# nano_hold_1_2.net
KiCad netlist of a schematic drawn in EAGLE
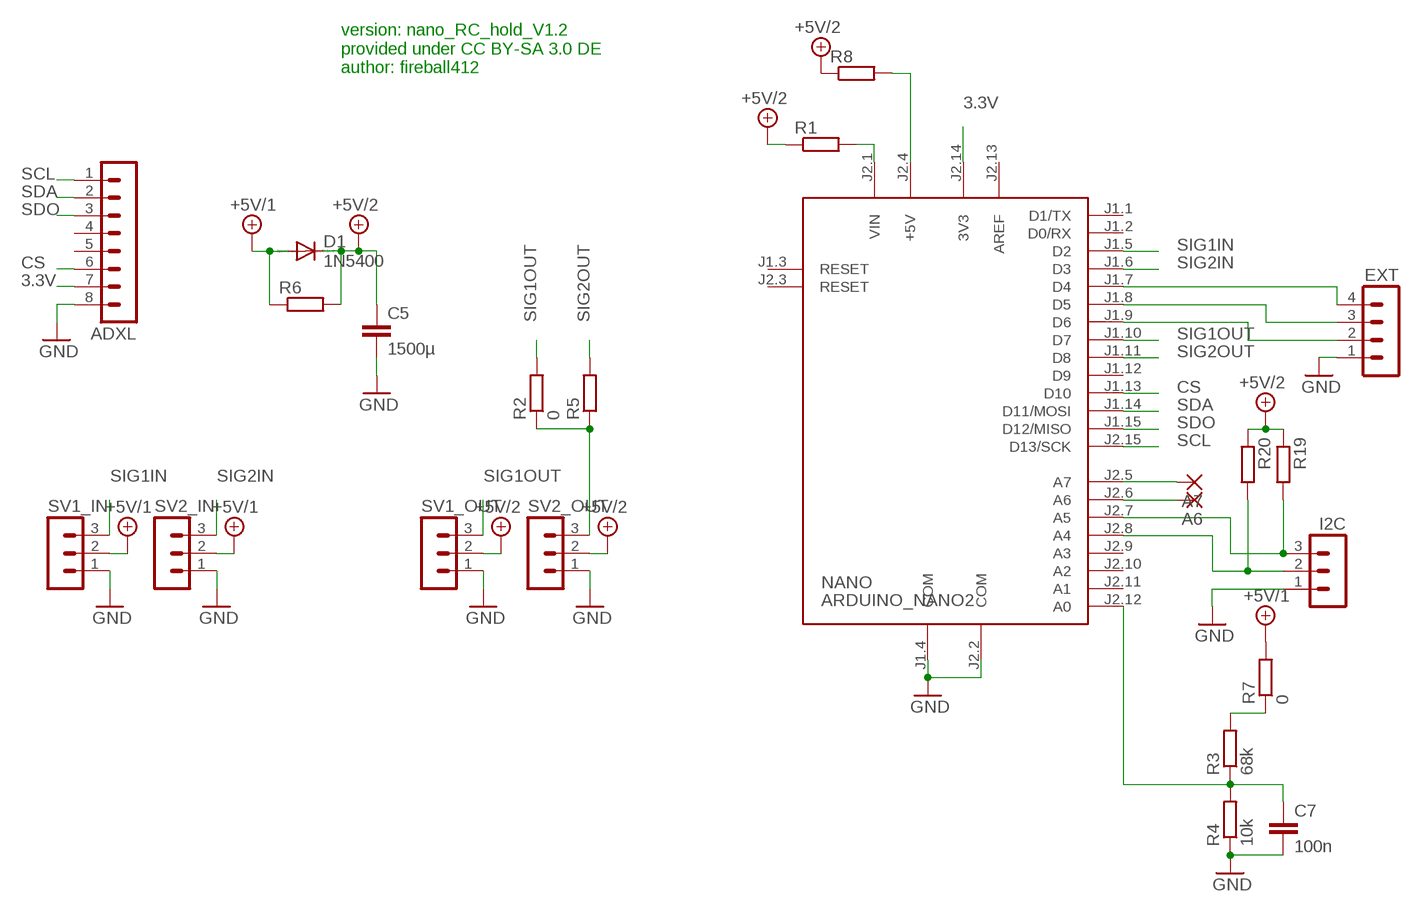
[diagram p0: schematic, sheet 1]

(export (version "E")
  (design (tool "Eeschema 10.0.6"))
  (components
    (comp (ref "A6")
      (value "WIREPAD2,15/1,0")
      (footprint "eagle-import:2,15_1,0")
      (libsource (lib "eagle-import") (part "WIREPAD2,15/1,0"))
    )
    (comp (ref "A7")
      (value "WIREPAD2,15/1,0")
      (footprint "eagle-import:2,15_1,0")
      (libsource (lib "eagle-import") (part "WIREPAD2,15/1,0"))
    )
    (comp (ref "ADXL")
      (value "MA08-1")
      (footprint "eagle-import:MA08-1")
      (libsource (lib "eagle-import") (part "MA08-1"))
    )
    (comp (ref "C5")
      (value "1500µ")
      (footprint "eagle-import:C050H075X075")
      (libsource (lib "eagle-import") (part "C-EU050H075X075"))
    )
    (comp (ref "C7")
      (value "100n")
      (footprint "eagle-import:C0805")
      (libsource (lib "eagle-import") (part "C-EUC0805"))
    )
    (comp (ref "D1")
      (value "1N5400")
      (footprint "eagle-import:DO201-15")
      (libsource (lib "eagle-import") (part "1N5400"))
    )
    (comp (ref "EXT")
      (value "MA04-1")
      (footprint "eagle-import:MA04-1")
      (libsource (lib "eagle-import") (part "MA04-1"))
    )
    (comp (ref "I2C")
      (value "MA03-1")
      (footprint "eagle-import:MA03-1")
      (libsource (lib "eagle-import") (part "MA03-1"))
    )
    (comp (ref "NANO")
      (value "ARDUINO_NANO2")
      (footprint "eagle-import:ARDUINO_NANO2")
      (libsource (lib "eagle-import") (part "ARDUINO_NANO2"))
    )
    (comp (ref "R1")
      (value "R-EU_R0805")
      (footprint "eagle-import:R0805")
      (libsource (lib "eagle-import") (part "R-EU_R0805"))
    )
    (comp (ref "R2")
      (value "0")
      (footprint "eagle-import:R0805")
      (libsource (lib "eagle-import") (part "R-EU_R0805"))
    )
    (comp (ref "R3")
      (value "68k")
      (footprint "eagle-import:R0805")
      (libsource (lib "eagle-import") (part "R-EU_R0805"))
    )
    (comp (ref "R4")
      (value "10k")
      (footprint "eagle-import:R0805")
      (libsource (lib "eagle-import") (part "R-EU_R0805"))
    )
    (comp (ref "R5")
      (value "R-EU_R0805")
      (footprint "eagle-import:R0805")
      (libsource (lib "eagle-import") (part "R-EU_R0805"))
    )
    (comp (ref "R6")
      (value "R-EU_R0805")
      (footprint "eagle-import:R0805")
      (libsource (lib "eagle-import") (part "R-EU_R0805"))
    )
    (comp (ref "R7")
      (value "0")
      (footprint "eagle-import:R0805")
      (libsource (lib "eagle-import") (part "R-EU_R0805"))
    )
    (comp (ref "R8")
      (value "R-EU_R0805")
      (footprint "eagle-import:R0805")
      (libsource (lib "eagle-import") (part "R-EU_R0805"))
    )
    (comp (ref "R19")
      (value "R-EU_R0805")
      (footprint "eagle-import:R0805")
      (libsource (lib "eagle-import") (part "R-EU_R0805"))
    )
    (comp (ref "R20")
      (value "R-EU_R0805")
      (footprint "eagle-import:R0805")
      (libsource (lib "eagle-import") (part "R-EU_R0805"))
    )
    (comp (ref "SV1_IN")
      (value "MA03-1")
      (footprint "eagle-import:MA03-1")
      (libsource (lib "eagle-import") (part "MA03-1"))
    )
    (comp (ref "SV1_OUT")
      (value "MA03-1")
      (footprint "eagle-import:MA03-1")
      (libsource (lib "eagle-import") (part "MA03-1"))
    )
    (comp (ref "SV2_IN")
      (value "MA03-1")
      (footprint "eagle-import:MA03-1")
      (libsource (lib "eagle-import") (part "MA03-1"))
    )
    (comp (ref "SV2_OUT")
      (value "MA03-1")
      (footprint "eagle-import:MA03-1")
      (libsource (lib "eagle-import") (part "MA03-1"))
    )
  )
  (nets
    (net (code "1") (name "+5V{slash}1") (class "Default")
      (node (ref "D1") (pin "A") (pinfunction "A_A") (pintype "passive"))
      (node (ref "R6") (pin "1") (pinfunction "1_1") (pintype "passive"))
      (node (ref "R7") (pin "2") (pinfunction "2_2") (pintype "passive"))
      (node (ref "SV1_IN") (pin "2") (pinfunction "2_2") (pintype "passive"))
      (node (ref "SV2_IN") (pin "2") (pinfunction "2_2") (pintype "passive"))
    )
    (net (code "2") (name "+5V{slash}2") (class "Default")
      (node (ref "C5") (pin "1") (pinfunction "1_1") (pintype "passive"))
      (node (ref "D1") (pin "C") (pinfunction "C_C") (pintype "passive"))
      (node (ref "R1") (pin "1") (pinfunction "1_1") (pintype "passive"))
      (node (ref "R19") (pin "1") (pinfunction "1_1") (pintype "passive"))
      (node (ref "R20") (pin "1") (pinfunction "1_1") (pintype "passive"))
      (node (ref "R6") (pin "2") (pinfunction "2_2") (pintype "passive"))
      (node (ref "R8") (pin "1") (pinfunction "1_1") (pintype "passive"))
      (node (ref "SV1_OUT") (pin "2") (pinfunction "2_2") (pintype "passive"))
      (node (ref "SV2_OUT") (pin "2") (pinfunction "2_2") (pintype "passive"))
    )
    (net (code "3") (name "/3.3V") (class "Default")
      (node (ref "ADXL") (pin "7") (pinfunction "7_7") (pintype "passive"))
      (node (ref "NANO") (pin "J2.14") (pinfunction "3V3_J2.14") (pintype "power_in"))
    )
    (net (code "4") (name "/AREF") (class "Default")
      (node (ref "NANO") (pin "J2.13") (pinfunction "AREF_J2.13") (pintype "power_in"))
    )
    (net (code "5") (name "/CS") (class "Default")
      (node (ref "ADXL") (pin "6") (pinfunction "6_6") (pintype "passive"))
      (node (ref "NANO") (pin "J1.13") (pinfunction "D10_J1.13") (pintype "bidirectional"))
    )
    (net (code "6") (name "/SCL") (class "Default")
      (node (ref "ADXL") (pin "1") (pinfunction "1_1") (pintype "passive"))
      (node (ref "NANO") (pin "J2.15") (pinfunction "D13/SCK_J2.15") (pintype "bidirectional"))
    )
    (net (code "7") (name "/SDA") (class "Default")
      (node (ref "ADXL") (pin "2") (pinfunction "2_2") (pintype "passive"))
      (node (ref "NANO") (pin "J1.14") (pinfunction "D11/MOSI_J1.14") (pintype "bidirectional"))
    )
    (net (code "8") (name "/SDO") (class "Default")
      (node (ref "ADXL") (pin "3") (pinfunction "3_3") (pintype "passive"))
      (node (ref "NANO") (pin "J1.15") (pinfunction "D12/MISO_J1.15") (pintype "bidirectional"))
    )
    (net (code "9") (name "/SIG1IN") (class "Default")
      (node (ref "NANO") (pin "J1.5") (pinfunction "D2_J1.5") (pintype "bidirectional"))
      (node (ref "SV1_IN") (pin "3") (pinfunction "3_3") (pintype "passive"))
    )
    (net (code "10") (name "/SIG1OUT") (class "Default")
      (node (ref "NANO") (pin "J1.10") (pinfunction "D7_J1.10") (pintype "bidirectional"))
      (node (ref "R2") (pin "2") (pinfunction "2_2") (pintype "passive"))
      (node (ref "SV1_OUT") (pin "3") (pinfunction "3_3") (pintype "passive"))
    )
    (net (code "11") (name "/SIG2IN") (class "Default")
      (node (ref "NANO") (pin "J1.6") (pinfunction "D3_J1.6") (pintype "bidirectional"))
      (node (ref "SV2_IN") (pin "3") (pinfunction "3_3") (pintype "passive"))
    )
    (net (code "12") (name "/SIG2OUT") (class "Default")
      (node (ref "NANO") (pin "J1.11") (pinfunction "D8_J1.11") (pintype "bidirectional"))
      (node (ref "R5") (pin "2") (pinfunction "2_2") (pintype "passive"))
    )
    (net (code "13") (name "GND") (class "Default")
      (node (ref "ADXL") (pin "8") (pinfunction "8_8") (pintype "passive"))
      (node (ref "C5") (pin "2") (pinfunction "2_2") (pintype "passive"))
      (node (ref "C7") (pin "2") (pinfunction "2_2") (pintype "passive"))
      (node (ref "EXT") (pin "1") (pinfunction "1_1") (pintype "passive"))
      (node (ref "I2C") (pin "1") (pinfunction "1_1") (pintype "passive"))
      (node (ref "NANO") (pin "J1.4") (pinfunction "COM_J1.4") (pintype "power_in"))
      (node (ref "NANO") (pin "J2.2") (pinfunction "COM_J2.2") (pintype "power_in"))
      (node (ref "R4") (pin "1") (pinfunction "1_1") (pintype "passive"))
      (node (ref "SV1_IN") (pin "1") (pinfunction "1_1") (pintype "passive"))
      (node (ref "SV1_OUT") (pin "1") (pinfunction "1_1") (pintype "passive"))
      (node (ref "SV2_IN") (pin "1") (pinfunction "1_1") (pintype "passive"))
      (node (ref "SV2_OUT") (pin "1") (pinfunction "1_1") (pintype "passive"))
    )
    (net (code "14") (name "Net-(A6-P)") (class "Default")
      (node (ref "A6") (pin "1") (pinfunction "P_1") (pintype "passive"))
      (node (ref "NANO") (pin "J2.6") (pinfunction "A6_J2.6") (pintype "bidirectional"))
    )
    (net (code "15") (name "Net-(A7-P)") (class "Default")
      (node (ref "A7") (pin "1") (pinfunction "P_1") (pintype "passive"))
      (node (ref "NANO") (pin "J2.5") (pinfunction "A7_J2.5") (pintype "bidirectional"))
    )
    (net (code "16") (name "Net-(NANO-+5V)") (class "Default")
      (node (ref "NANO") (pin "J2.4") (pinfunction "+5V_J2.4") (pintype "power_in"))
      (node (ref "R8") (pin "2") (pinfunction "2_2") (pintype "passive"))
    )
    (net (code "17") (name "Net-(NANO-A0)") (class "Default")
      (node (ref "C7") (pin "1") (pinfunction "1_1") (pintype "passive"))
      (node (ref "NANO") (pin "J2.12") (pinfunction "A0_J2.12") (pintype "bidirectional"))
      (node (ref "R3") (pin "1") (pinfunction "1_1") (pintype "passive"))
      (node (ref "R4") (pin "2") (pinfunction "2_2") (pintype "passive"))
    )
    (net (code "18") (name "Net-(NANO-A4)") (class "Default")
      (node (ref "I2C") (pin "2") (pinfunction "2_2") (pintype "passive"))
      (node (ref "NANO") (pin "J2.8") (pinfunction "A4_J2.8") (pintype "bidirectional"))
      (node (ref "R20") (pin "2") (pinfunction "2_2") (pintype "passive"))
    )
    (net (code "19") (name "Net-(NANO-A5)") (class "Default")
      (node (ref "I2C") (pin "3") (pinfunction "3_3") (pintype "passive"))
      (node (ref "NANO") (pin "J2.7") (pinfunction "A5_J2.7") (pintype "bidirectional"))
      (node (ref "R19") (pin "2") (pinfunction "2_2") (pintype "passive"))
    )
    (net (code "20") (name "Net-(NANO-D4)") (class "Default")
      (node (ref "EXT") (pin "4") (pinfunction "4_4") (pintype "passive"))
      (node (ref "NANO") (pin "J1.7") (pinfunction "D4_J1.7") (pintype "bidirectional"))
    )
    (net (code "21") (name "Net-(NANO-D5)") (class "Default")
      (node (ref "EXT") (pin "3") (pinfunction "3_3") (pintype "passive"))
      (node (ref "NANO") (pin "J1.8") (pinfunction "D5_J1.8") (pintype "bidirectional"))
    )
    (net (code "22") (name "Net-(NANO-D6)") (class "Default")
      (node (ref "EXT") (pin "2") (pinfunction "2_2") (pintype "passive"))
      (node (ref "NANO") (pin "J1.9") (pinfunction "D6_J1.9") (pintype "bidirectional"))
    )
    (net (code "23") (name "Net-(NANO-VIN)") (class "Default")
      (node (ref "NANO") (pin "J2.1") (pinfunction "VIN_J2.1") (pintype "power_in"))
      (node (ref "R1") (pin "2") (pinfunction "2_2") (pintype "passive"))
    )
    (net (code "24") (name "Net-(R2-Pad1)") (class "Default")
      (node (ref "R2") (pin "1") (pinfunction "1_1") (pintype "passive"))
      (node (ref "R5") (pin "1") (pinfunction "1_1") (pintype "passive"))
      (node (ref "SV2_OUT") (pin "3") (pinfunction "3_3") (pintype "passive"))
    )
    (net (code "25") (name "Net-(R3-Pad2)") (class "Default")
      (node (ref "R3") (pin "2") (pinfunction "2_2") (pintype "passive"))
      (node (ref "R7") (pin "1") (pinfunction "1_1") (pintype "passive"))
    )
    (net (code "26") (name "unconnected-(ADXL-Pad4)") (class "Default")
      (node (ref "ADXL") (pin "4") (pinfunction "4_4") (pintype "passive"))
    )
    (net (code "27") (name "unconnected-(ADXL-Pad5)") (class "Default")
      (node (ref "ADXL") (pin "5") (pinfunction "5_5") (pintype "passive"))
    )
    (net (code "28") (name "unconnected-(NANO-A1-PadJ2.11)") (class "Default")
      (node (ref "NANO") (pin "J2.11") (pinfunction "A1_J2.11") (pintype "bidirectional"))
    )
    (net (code "29") (name "unconnected-(NANO-A2-PadJ2.10)") (class "Default")
      (node (ref "NANO") (pin "J2.10") (pinfunction "A2_J2.10") (pintype "bidirectional"))
    )
    (net (code "30") (name "unconnected-(NANO-A3-PadJ2.9)") (class "Default")
      (node (ref "NANO") (pin "J2.9") (pinfunction "A3_J2.9") (pintype "bidirectional"))
    )
    (net (code "31") (name "unconnected-(NANO-D0{slash}RX-PadJ1.2)") (class "Default")
      (node (ref "NANO") (pin "J1.2") (pinfunction "D0/RX_J1.2") (pintype "bidirectional"))
    )
    (net (code "32") (name "unconnected-(NANO-D1{slash}TX-PadJ1.1)") (class "Default")
      (node (ref "NANO") (pin "J1.1") (pinfunction "D1/TX_J1.1") (pintype "bidirectional"))
    )
    (net (code "33") (name "unconnected-(NANO-D9-PadJ1.12)") (class "Default")
      (node (ref "NANO") (pin "J1.12") (pinfunction "D9_J1.12") (pintype "bidirectional"))
    )
    (net (code "34") (name "unconnected-(NANO-RESET-PadJ1.3)") (class "Default")
      (node (ref "NANO") (pin "J1.3") (pinfunction "RESET_J1.3") (pintype "bidirectional"))
    )
    (net (code "35") (name "unconnected-(NANO-RESET-PadJ2.3)") (class "Default")
      (node (ref "NANO") (pin "J2.3") (pinfunction "RESET_J2.3") (pintype "bidirectional"))
    )
  )
)
